# UI.net
KiCad netlist of a schematic drawn in Altium Designer
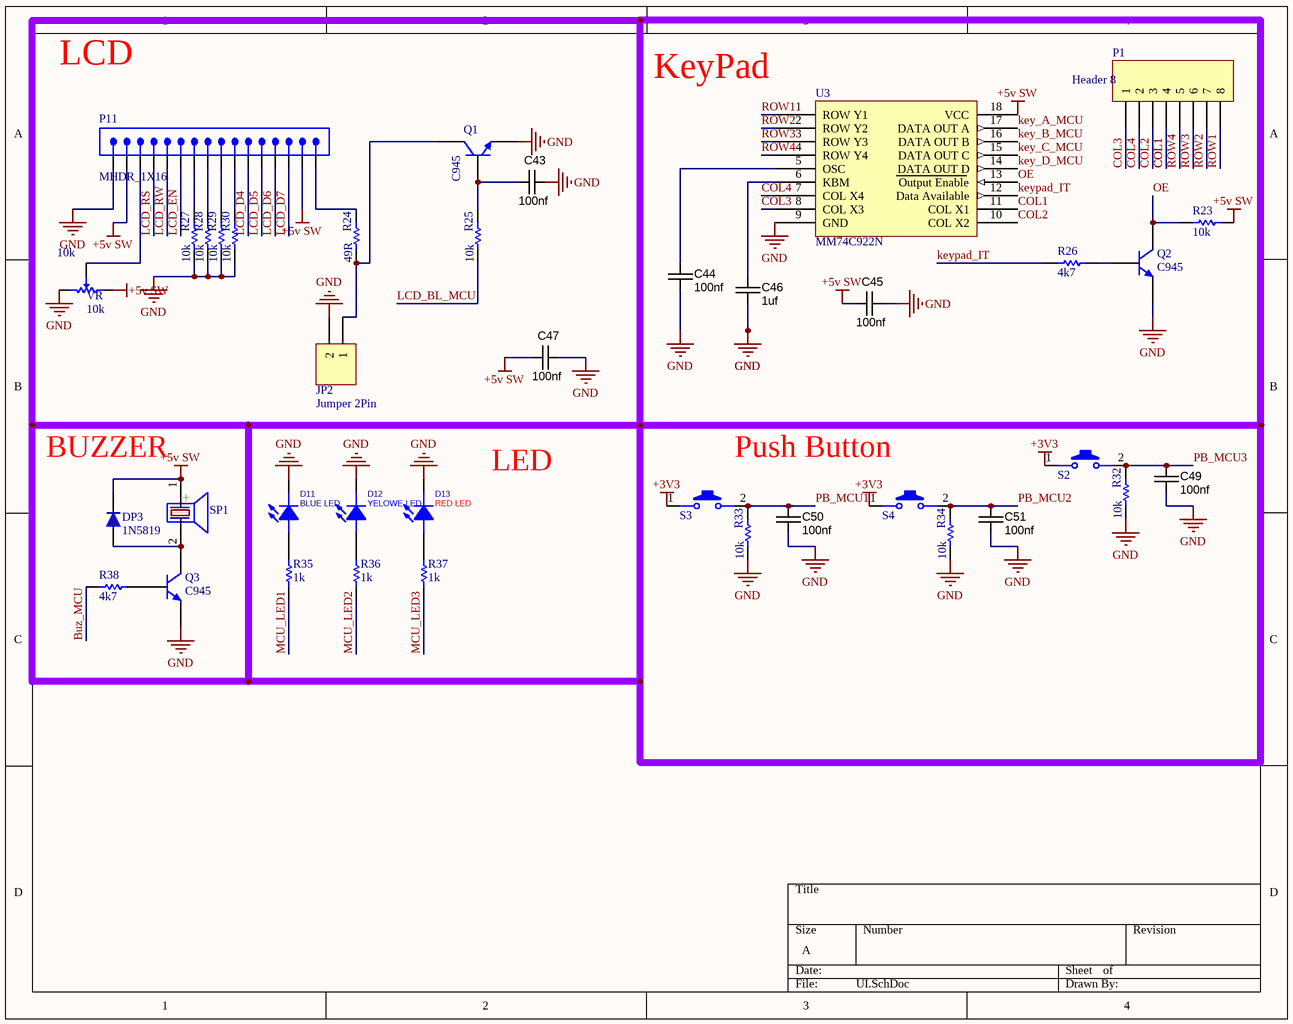
[diagram p0: UI.SchDoc]

(export (version "E")
  (design (tool "Eeschema 10.0.6"))
  (components
    (comp (ref "C43")
      (value "100nf")
      (footprint "CAPC1608X90N")
      (description "Capacitor SMD Cer 100nF 10% 50V X7R 0603")
      (fields (field (name "TOLERANCE") "±10%"))
      (libsource (lib "altium-import") (part "root_1_CAPC_100n_0603_X7R_50V_10%_"))
    )
    (comp (ref "C44")
      (value "100nf")
      (footprint "CAPC1608X90N")
      (description "Capacitor SMD Cer 100nF 10% 50V X7R 0603")
      (fields (field (name "TOLERANCE") "±10%"))
      (libsource (lib "altium-import") (part "root_0_CAPC_100n_0603_X7R_50V_10%_"))
    )
    (comp (ref "C45")
      (value "100nf")
      (footprint "CAPC1608X90N")
      (description "Capacitor SMD Cer 100nF 10% 50V X7R 0603")
      (fields (field (name "TOLERANCE") "±10%"))
      (libsource (lib "altium-import") (part "root_1_CAPC_100n_0603_X7R_50V_10%_"))
    )
    (comp (ref "C46")
      (value "1uf")
      (footprint "CAPC1608X90N")
      (description "Capacitor SMD Cer 100nF 10% 50V X7R 0603")
      (fields (field (name "TOLERANCE") "±10%"))
      (libsource (lib "altium-import") (part "root_0_CAPC_100n_0603_X7R_50V_10%_"))
    )
    (comp (ref "C47")
      (value "100nf")
      (footprint "CAPC1608X90N")
      (description "Capacitor SMD Cer 100nF 10% 50V X7R 0603")
      (fields (field (name "TOLERANCE") "±10%"))
      (libsource (lib "altium-import") (part "root_1_CAPC_100n_0603_X7R_50V_10%_"))
    )
    (comp (ref "C49")
      (value "100nf")
      (footprint "CAPC1608X90N")
      (description "Capacitor SMD Cer 100nF 10% 50V X7R 0603")
      (fields (field (name "TOLERANCE") "±10%"))
      (libsource (lib "altium-import") (part "root_2_CAPC_100n_0603_X7R_50V_10%_"))
    )
    (comp (ref "C50")
      (value "100nf")
      (footprint "CAPC1608X90N")
      (description "Capacitor SMD Cer 100nF 10% 50V X7R 0603")
      (fields (field (name "TOLERANCE") "±10%"))
      (libsource (lib "altium-import") (part "root_2_CAPC_100n_0603_X7R_50V_10%_"))
    )
    (comp (ref "C51")
      (value "100nf")
      (footprint "CAPC1608X90N")
      (description "Capacitor SMD Cer 100nF 10% 50V X7R 0603")
      (fields (field (name "TOLERANCE") "±10%"))
      (libsource (lib "altium-import") (part "root_2_CAPC_100n_0603_X7R_50V_10%_"))
    )
    (comp (ref "D11")
      (value "BLUE LED")
      (footprint "LED5MM_BLUE")
      (description "LED LIGHTING")
      (fields (field (name "DESIGNER") "Abbas Basereh"))
      (libsource (lib "altium-import") (part "root_1_LED5MM_"))
    )
    (comp (ref "D12")
      (value "YELOWE LED")
      (footprint "LED5MM_YELLOW")
      (description "LED LIGHTING")
      (fields (field (name "DESIGNER") "Abbas Basereh"))
      (libsource (lib "altium-import") (part "root_1_LED5MM_"))
    )
    (comp (ref "D13")
      (value "RED LED")
      (footprint "LED5MM_RED")
      (description "LED LIGHTING")
      (fields (field (name "DESIGNER") "Abbas Basereh"))
      (libsource (lib "altium-import") (part "root_1_LED5MM_"))
    )
    (comp (ref "DP3")
      (value "1N5819")
      (footprint "430X270D")
      (description "Schottkey Rectifiers")
      (fields (field (name "DESIGNER") "Abbas Basereh"))
      (libsource (lib "2017AbbasBasereh9365731239 -ver1") (part "1N5819"))
    )
    (comp (ref "JP2")
      (value "Jumper 2Pin")
      (footprint "Jumper Small - 2.54 - Blue")
      (description "Jumper, 2-Pin")
      (fields (field (name "DESIGNER") "Abbas Basereh"))
      (libsource (lib "altium-import") (part "root_3_Jumper 2Pin_"))
    )
    (comp (ref "P1")
      (value "Header 8")
      (footprint "HDR1X8")
      (description "Header, 8-Pin")
      (fields (field (name "PUBLISHER") "Altium Limited"))
      (libsource (lib "altium-import") (part "root_1_Header 8_"))
    )
    (comp (ref "P11")
      (value "MHDR_1X16")
      (footprint "MHDR1X16-254P")
      (description "Male Header 1X16")
      (libsource (lib "SJ Sockets & Connectors") (part "MHDR_1X16"))
    )
    (comp (ref "Q1")
      (value "C945")
      (footprint "SOT23_N")
      (description "NPN Silicon Epitaxial Planar Transistor")
      (fields (field (name "PUBLISHER") "Abbas Basereh"))
      (libsource (lib "altium-import") (part "root_1_C945_"))
    )
    (comp (ref "Q2")
      (value "C945")
      (footprint "SOT23_N")
      (description "NPN Silicon Epitaxial Planar Transistor")
      (fields (field (name "PUBLISHER") "Abbas Basereh"))
      (libsource (lib "altium-import") (part "root_0_C945_"))
    )
    (comp (ref "Q3")
      (value "C945")
      (footprint "SOT23_N")
      (description "NPN Silicon Epitaxial Planar Transistor")
      (fields (field (name "PUBLISHER") "Abbas Basereh"))
      (libsource (lib "altium-import") (part "root_0_C945_"))
    )
    (comp (ref "R23")
      (value "10k")
      (footprint "Resistor_SMD_0603 (1608)")
      (description "Resistor 0603")
      (fields (field (name "PUBLISHER") "Seyed Razi Vesali") (field (name "EMAIL") "razi.vesali@gmail.com"))
      (libsource (lib "resistors") (part "Resistor"))
    )
    (comp (ref "R24")
      (value "49R")
      (footprint "Resistor_SMD_0603 (1608)")
      (description "Resistor 0603")
      (fields (field (name "PUBLISHER") "Seyed Razi Vesali") (field (name "EMAIL") "razi.vesali@gmail.com"))
      (libsource (lib "resistors") (part "Resistor"))
    )
    (comp (ref "R25")
      (value "10k")
      (footprint "Resistor_SMD_0603 (1608)")
      (description "Resistor 0603")
      (fields (field (name "PUBLISHER") "Seyed Razi Vesali") (field (name "EMAIL") "razi.vesali@gmail.com"))
      (libsource (lib "resistors") (part "Resistor"))
    )
    (comp (ref "R26")
      (value "4k7")
      (footprint "Resistor_SMD_0603 (1608)")
      (description "Resistor 0603")
      (fields (field (name "PUBLISHER") "Seyed Razi Vesali") (field (name "EMAIL") "razi.vesali@gmail.com"))
      (libsource (lib "resistors") (part "Resistor"))
    )
    (comp (ref "R27")
      (value "10k")
      (footprint "Resistor_SMD_0603 (1608)")
      (description "Resistor 0603")
      (fields (field (name "PUBLISHER") "Seyed Razi Vesali") (field (name "EMAIL") "razi.vesali@gmail.com"))
      (libsource (lib "resistors") (part "Resistor"))
    )
    (comp (ref "R28")
      (value "10k")
      (footprint "Resistor_SMD_0603 (1608)")
      (description "Resistor 0603")
      (fields (field (name "PUBLISHER") "Seyed Razi Vesali") (field (name "EMAIL") "razi.vesali@gmail.com"))
      (libsource (lib "resistors") (part "Resistor"))
    )
    (comp (ref "R29")
      (value "10k")
      (footprint "Resistor_SMD_0603 (1608)")
      (description "Resistor 0603")
      (fields (field (name "PUBLISHER") "Seyed Razi Vesali") (field (name "EMAIL") "razi.vesali@gmail.com"))
      (libsource (lib "resistors") (part "Resistor"))
    )
    (comp (ref "R30")
      (value "10k")
      (footprint "Resistor_SMD_0603 (1608)")
      (description "Resistor 0603")
      (fields (field (name "PUBLISHER") "Seyed Razi Vesali") (field (name "EMAIL") "razi.vesali@gmail.com"))
      (libsource (lib "resistors") (part "Resistor"))
    )
    (comp (ref "R32")
      (value "10k")
      (footprint "Resistor_SMD_0603 (1608)")
      (description "Resistor 0603")
      (fields (field (name "PUBLISHER") "Seyed Razi Vesali") (field (name "EMAIL") "razi.vesali@gmail.com"))
      (libsource (lib "resistors") (part "Resistor"))
    )
    (comp (ref "R33")
      (value "10k")
      (footprint "Resistor_SMD_0603 (1608)")
      (description "Resistor 0603")
      (fields (field (name "PUBLISHER") "Seyed Razi Vesali") (field (name "EMAIL") "razi.vesali@gmail.com"))
      (libsource (lib "resistors") (part "Resistor"))
    )
    (comp (ref "R34")
      (value "10k")
      (footprint "Resistor_SMD_0603 (1608)")
      (description "Resistor 0603")
      (fields (field (name "PUBLISHER") "Seyed Razi Vesali") (field (name "EMAIL") "razi.vesali@gmail.com"))
      (libsource (lib "resistors") (part "Resistor"))
    )
    (comp (ref "R35")
      (value "1k")
      (footprint "Resistor_SMD_0603 (1608)")
      (description "Resistor 0603")
      (fields (field (name "PUBLISHER") "Seyed Razi Vesali") (field (name "EMAIL") "razi.vesali@gmail.com"))
      (libsource (lib "resistors") (part "Resistor"))
    )
    (comp (ref "R36")
      (value "1k")
      (footprint "Resistor_SMD_0603 (1608)")
      (description "Resistor 0603")
      (fields (field (name "PUBLISHER") "Seyed Razi Vesali") (field (name "EMAIL") "razi.vesali@gmail.com"))
      (libsource (lib "resistors") (part "Resistor"))
    )
    (comp (ref "R37")
      (value "1k")
      (footprint "Resistor_SMD_0603 (1608)")
      (description "Resistor 0603")
      (fields (field (name "PUBLISHER") "Seyed Razi Vesali") (field (name "EMAIL") "razi.vesali@gmail.com"))
      (libsource (lib "resistors") (part "Resistor"))
    )
    (comp (ref "R38")
      (value "4k7")
      (footprint "Resistor_SMD_0603 (1608)")
      (description "Resistor 0603")
      (fields (field (name "PUBLISHER") "Seyed Razi Vesali") (field (name "EMAIL") "razi.vesali@gmail.com"))
      (libsource (lib "resistors") (part "Resistor"))
    )
    (comp (ref "S2")
      (value "SW_PB2")
      (footprint "THT_ALPS_SKQKAJD010")
      (description "2 Pin Push Button Switch")
      (fields (field (name "DESIGNER") "Eng. Saeid Jorablo"))
      (libsource (lib "SJ Switches") (part "SW_PB2"))
    )
    (comp (ref "S3")
      (value "SW_PB2")
      (footprint "THT_ALPS_SKQKAJD010")
      (description "2 Pin Push Button Switch")
      (fields (field (name "DESIGNER") "Eng. Saeid Jorablo"))
      (libsource (lib "SJ Switches") (part "SW_PB2"))
    )
    (comp (ref "S4")
      (value "SW_PB2")
      (footprint "THT_ALPS_SKQKAJD010")
      (description "2 Pin Push Button Switch")
      (fields (field (name "DESIGNER") "Eng. Saeid Jorablo"))
      (libsource (lib "SJ Switches") (part "SW_PB2"))
    )
    (comp (ref "SP1")
      (value "~")
      (footprint "BUZZER 7.62mm DC")
      (description "PIEZO BUZZER ACTIVE")
      (fields (field (name "DESIGNER") "Abbas Basereh") (field (name "PUBLISHER") "Abbas Basereh"))
      (libsource (lib "altium-import") (part "root_0_PIEZO BUZZER_"))
    )
    (comp (ref "U3")
      (value "MM74C922N")
      (footprint "DIP18")
      (description "16-Key Encoder")
      (libsource (lib "Altium") (part "MM74c922N_Fairchild"))
    )
    (comp (ref "VR")
      (value "10k")
      (footprint "Multi Turn")
      (description "Multi Turn")
      (fields
        (field (name "ALTIUM_VALUE") "10k")
        (field (name "PUBLISHER") "Seyed Razi vesali (SRV)")
        (field (name "EMAIL") "Razi.vesali@gmail.com")
      )
      (libsource (lib "resistors") (part "Multi Turn"))
    )
  )
  (nets
    (net (code "1") (name "+3V3") (class "Default")
      (node (ref "S2") (pin "1") (pinfunction "Button_1") (pintype "passive"))
      (node (ref "S3") (pin "1") (pinfunction "Button_1") (pintype "passive"))
      (node (ref "S4") (pin "1") (pinfunction "Button_1") (pintype "passive"))
    )
    (net (code "2") (name "+5v SW") (class "Default")
      (node (ref "C45") (pin "1") (pintype "passive"))
      (node (ref "C47") (pin "1") (pintype "passive"))
      (node (ref "DP3") (pin "2") (pintype "passive"))
      (node (ref "P11") (pin "15") (pinfunction "15_15") (pintype "passive"))
      (node (ref "P11") (pin "2") (pinfunction "2_2") (pintype "passive"))
      (node (ref "R23") (pin "1") (pinfunction "1_1") (pintype "passive"))
      (node (ref "SP1") (pin "1") (pinfunction "+_1") (pintype "passive"))
      (node (ref "U3") (pin "18") (pinfunction "VCC_18") (pintype "power_in"))
      (node (ref "VR") (pin "1") (pinfunction "CCW_1") (pintype "passive"))
    )
    (net (code "4") (name "/Buz_MCU") (class "Default")
      (node (ref "R38") (pin "1") (pinfunction "1_1") (pintype "passive"))
    )
    (net (code "5") (name "/COL1") (class "Default")
      (node (ref "P1") (pin "4") (pinfunction "4_4") (pintype "passive"))
      (node (ref "U3") (pin "11") (pinfunction "COL_X1_11") (pintype "passive"))
    )
    (net (code "6") (name "/COL2") (class "Default")
      (node (ref "P1") (pin "3") (pinfunction "3_3") (pintype "passive"))
      (node (ref "U3") (pin "10") (pinfunction "COL_X2_10") (pintype "passive"))
    )
    (net (code "7") (name "/COL3") (class "Default")
      (node (ref "P1") (pin "1") (pinfunction "1_1") (pintype "passive"))
      (node (ref "U3") (pin "8") (pinfunction "COL_X3_8") (pintype "passive"))
    )
    (net (code "8") (name "/COL4") (class "Default")
      (node (ref "P1") (pin "2") (pinfunction "2_2") (pintype "passive"))
      (node (ref "U3") (pin "7") (pinfunction "COL_X4_7") (pintype "passive"))
    )
    (net (code "9") (name "/LCD_BL_MCU") (class "Default")
      (node (ref "R25") (pin "2") (pinfunction "2_2") (pintype "passive"))
    )
    (net (code "10") (name "/LCD_D4") (class "Default")
      (node (ref "P11") (pin "11") (pinfunction "11_11") (pintype "passive"))
    )
    (net (code "11") (name "/LCD_D5") (class "Default")
      (node (ref "P11") (pin "12") (pinfunction "12_12") (pintype "passive"))
    )
    (net (code "12") (name "/LCD_D6") (class "Default")
      (node (ref "P11") (pin "13") (pinfunction "13_13") (pintype "passive"))
    )
    (net (code "13") (name "/LCD_D7") (class "Default")
      (node (ref "P11") (pin "14") (pinfunction "14_14") (pintype "passive"))
    )
    (net (code "14") (name "/LCD_EN") (class "Default")
      (node (ref "P11") (pin "6") (pinfunction "6_6") (pintype "passive"))
    )
    (net (code "15") (name "/LCD_RS") (class "Default")
      (node (ref "P11") (pin "4") (pinfunction "4_4") (pintype "passive"))
    )
    (net (code "16") (name "/LCD_RW") (class "Default")
      (node (ref "P11") (pin "5") (pinfunction "5_5") (pintype "passive"))
    )
    (net (code "17") (name "/MCU_LED1") (class "Default")
      (node (ref "R35") (pin "1") (pinfunction "1_1") (pintype "passive"))
    )
    (net (code "18") (name "/MCU_LED2") (class "Default")
      (node (ref "R36") (pin "1") (pinfunction "1_1") (pintype "passive"))
    )
    (net (code "19") (name "/MCU_LED3") (class "Default")
      (node (ref "R37") (pin "1") (pinfunction "1_1") (pintype "passive"))
    )
    (net (code "20") (name "/OE") (class "Default")
      (node (ref "Q2") (pin "3") (pinfunction "C_3") (pintype "passive"))
      (node (ref "R23") (pin "2") (pinfunction "2_2") (pintype "passive"))
      (node (ref "U3") (pin "13") (pinfunction "Output_Enable_13") (pintype "input"))
    )
    (net (code "21") (name "/PB_MCU1") (class "Default")
      (node (ref "C50") (pin "2") (pintype "passive"))
      (node (ref "R33") (pin "1") (pinfunction "1_1") (pintype "passive"))
      (node (ref "S3") (pin "2") (pinfunction "2_2") (pintype "passive"))
    )
    (net (code "22") (name "/PB_MCU2") (class "Default")
      (node (ref "C51") (pin "2") (pintype "passive"))
      (node (ref "R34") (pin "1") (pinfunction "1_1") (pintype "passive"))
      (node (ref "S4") (pin "2") (pinfunction "2_2") (pintype "passive"))
    )
    (net (code "23") (name "/PB_MCU3") (class "Default")
      (node (ref "C49") (pin "2") (pintype "passive"))
      (node (ref "R32") (pin "1") (pinfunction "1_1") (pintype "passive"))
      (node (ref "S2") (pin "2") (pinfunction "2_2") (pintype "passive"))
    )
    (net (code "24") (name "/ROW1") (class "Default")
      (node (ref "P1") (pin "8") (pinfunction "8_8") (pintype "passive"))
      (node (ref "U3") (pin "1") (pinfunction "ROW_Y1_1") (pintype "passive"))
    )
    (net (code "25") (name "/ROW2") (class "Default")
      (node (ref "P1") (pin "7") (pinfunction "7_7") (pintype "passive"))
      (node (ref "U3") (pin "2") (pinfunction "ROW_Y2_2") (pintype "passive"))
    )
    (net (code "26") (name "/ROW3") (class "Default")
      (node (ref "P1") (pin "6") (pinfunction "6_6") (pintype "passive"))
      (node (ref "U3") (pin "3") (pinfunction "ROW_Y3_3") (pintype "passive"))
    )
    (net (code "27") (name "/ROW4") (class "Default")
      (node (ref "P1") (pin "5") (pinfunction "5_5") (pintype "passive"))
      (node (ref "U3") (pin "4") (pinfunction "ROW_Y4_4") (pintype "passive"))
    )
    (net (code "28") (name "/key_A_MCU") (class "Default")
      (node (ref "U3") (pin "17") (pinfunction "DATA_OUT_A_17") (pintype "output"))
    )
    (net (code "29") (name "/key_B_MCU") (class "Default")
      (node (ref "U3") (pin "16") (pinfunction "DATA_OUT_B_16") (pintype "output"))
    )
    (net (code "30") (name "/key_C_MCU") (class "Default")
      (node (ref "U3") (pin "15") (pinfunction "DATA_OUT_C_15") (pintype "output"))
    )
    (net (code "31") (name "/key_D_MCU") (class "Default")
      (node (ref "U3") (pin "14") (pinfunction "DATA_OUT_D_14") (pintype "output"))
    )
    (net (code "32") (name "/keypad_IT") (class "Default")
      (node (ref "R26") (pin "1") (pinfunction "1_1") (pintype "passive"))
      (node (ref "U3") (pin "12") (pinfunction "Data_Available_12") (pintype "output"))
    )
    (net (code "33") (name "GND") (class "Default")
      (node (ref "C43") (pin "2") (pintype "passive"))
      (node (ref "C44") (pin "2") (pintype "passive"))
      (node (ref "C45") (pin "2") (pintype "passive"))
      (node (ref "C46") (pin "2") (pintype "passive"))
      (node (ref "C47") (pin "2") (pintype "passive"))
      (node (ref "C49") (pin "1") (pintype "passive"))
      (node (ref "C50") (pin "1") (pintype "passive"))
      (node (ref "C51") (pin "1") (pintype "passive"))
      (node (ref "D11") (pin "2") (pinfunction "CATHODE_2") (pintype "passive"))
      (node (ref "D12") (pin "2") (pinfunction "CATHODE_2") (pintype "passive"))
      (node (ref "D13") (pin "2") (pinfunction "CATHODE_2") (pintype "passive"))
      (node (ref "JP2") (pin "2") (pinfunction "2_2") (pintype "passive"))
      (node (ref "P11") (pin "1") (pinfunction "1_1") (pintype "passive"))
      (node (ref "Q1") (pin "2") (pinfunction "E_2") (pintype "passive"))
      (node (ref "Q2") (pin "2") (pinfunction "E_2") (pintype "passive"))
      (node (ref "Q3") (pin "2") (pinfunction "E_2") (pintype "passive"))
      (node (ref "R27") (pin "2") (pinfunction "2_2") (pintype "passive"))
      (node (ref "R28") (pin "2") (pinfunction "2_2") (pintype "passive"))
      (node (ref "R29") (pin "2") (pinfunction "2_2") (pintype "passive"))
      (node (ref "R30") (pin "2") (pinfunction "2_2") (pintype "passive"))
      (node (ref "R32") (pin "2") (pinfunction "2_2") (pintype "passive"))
      (node (ref "R33") (pin "2") (pinfunction "2_2") (pintype "passive"))
      (node (ref "R34") (pin "2") (pinfunction "2_2") (pintype "passive"))
      (node (ref "U3") (pin "9") (pinfunction "GND_9") (pintype "power_in"))
      (node (ref "VR") (pin "2") (pinfunction "CW_2") (pintype "passive"))
    )
    (net (code "34") (name "Net-(D11-ANODE)") (class "Default")
      (node (ref "D11") (pin "1") (pinfunction "ANODE_1") (pintype "passive"))
      (node (ref "R35") (pin "2") (pinfunction "2_2") (pintype "passive"))
    )
    (net (code "35") (name "Net-(D12-ANODE)") (class "Default")
      (node (ref "D12") (pin "1") (pinfunction "ANODE_1") (pintype "passive"))
      (node (ref "R36") (pin "2") (pinfunction "2_2") (pintype "passive"))
    )
    (net (code "36") (name "Net-(D13-ANODE)") (class "Default")
      (node (ref "D13") (pin "1") (pinfunction "ANODE_1") (pintype "passive"))
      (node (ref "R37") (pin "2") (pinfunction "2_2") (pintype "passive"))
    )
    (net (code "37") (name "Net-(P11-Pad7)") (class "Default")
      (node (ref "P11") (pin "7") (pinfunction "7_7") (pintype "passive"))
      (node (ref "R27") (pin "1") (pinfunction "1_1") (pintype "passive"))
    )
    (net (code "38") (name "Net-(P11-Pad8)") (class "Default")
      (node (ref "P11") (pin "8") (pinfunction "8_8") (pintype "passive"))
      (node (ref "R28") (pin "1") (pinfunction "1_1") (pintype "passive"))
    )
    (net (code "39") (name "Net-(P11-Pad9)") (class "Default")
      (node (ref "P11") (pin "9") (pinfunction "9_9") (pintype "passive"))
      (node (ref "R29") (pin "1") (pinfunction "1_1") (pintype "passive"))
    )
    (net (code "40") (name "Net-(P11-Pad10)") (class "Default")
      (node (ref "P11") (pin "10") (pinfunction "10_10") (pintype "passive"))
      (node (ref "R30") (pin "1") (pinfunction "1_1") (pintype "passive"))
    )
    (net (code "41") (name "Net-(P11-Pad16)") (class "Default")
      (node (ref "P11") (pin "16") (pinfunction "16_16") (pintype "passive"))
      (node (ref "R24") (pin "1") (pinfunction "1_1") (pintype "passive"))
    )
    (net (code "42") (name "Net-(Q1-B)") (class "Default")
      (node (ref "C43") (pin "1") (pintype "passive"))
      (node (ref "Q1") (pin "1") (pinfunction "B_1") (pintype "passive"))
      (node (ref "R25") (pin "1") (pinfunction "1_1") (pintype "passive"))
    )
    (net (code "43") (name "Net-(Q1-C)") (class "Default")
      (node (ref "JP2") (pin "1") (pinfunction "1_1") (pintype "passive"))
      (node (ref "Q1") (pin "3") (pinfunction "C_3") (pintype "passive"))
      (node (ref "R24") (pin "2") (pinfunction "2_2") (pintype "passive"))
    )
    (net (code "44") (name "Net-(Q2-B)") (class "Default")
      (node (ref "Q2") (pin "1") (pinfunction "B_1") (pintype "passive"))
      (node (ref "R26") (pin "2") (pinfunction "2_2") (pintype "passive"))
    )
    (net (code "45") (name "Net-(Q3-B)") (class "Default")
      (node (ref "Q3") (pin "1") (pinfunction "B_1") (pintype "passive"))
      (node (ref "R38") (pin "2") (pinfunction "2_2") (pintype "passive"))
    )
    (net (code "46") (name "Net-(Q3-C)") (class "Default")
      (node (ref "DP3") (pin "1") (pintype "passive"))
      (node (ref "Q3") (pin "3") (pinfunction "C_3") (pintype "passive"))
      (node (ref "SP1") (pin "2") (pinfunction "-_2") (pintype "passive"))
    )
    (net (code "47") (name "Net-(U3-KBM)") (class "Default")
      (node (ref "C46") (pin "1") (pintype "passive"))
      (node (ref "U3") (pin "6") (pinfunction "KBM_6") (pintype "passive"))
    )
    (net (code "48") (name "Net-(U3-OSC)") (class "Default")
      (node (ref "C44") (pin "1") (pintype "passive"))
      (node (ref "U3") (pin "5") (pinfunction "OSC_5") (pintype "passive"))
    )
    (net (code "49") (name "Net-(VR-Setpoint)") (class "Default")
      (node (ref "P11") (pin "3") (pinfunction "3_3") (pintype "passive"))
      (node (ref "VR") (pin "3") (pinfunction "Setpoint_3") (pintype "passive"))
    )
  )
)
